# Sheet1.net
KiCad netlist of a schematic drawn in Altium Designer
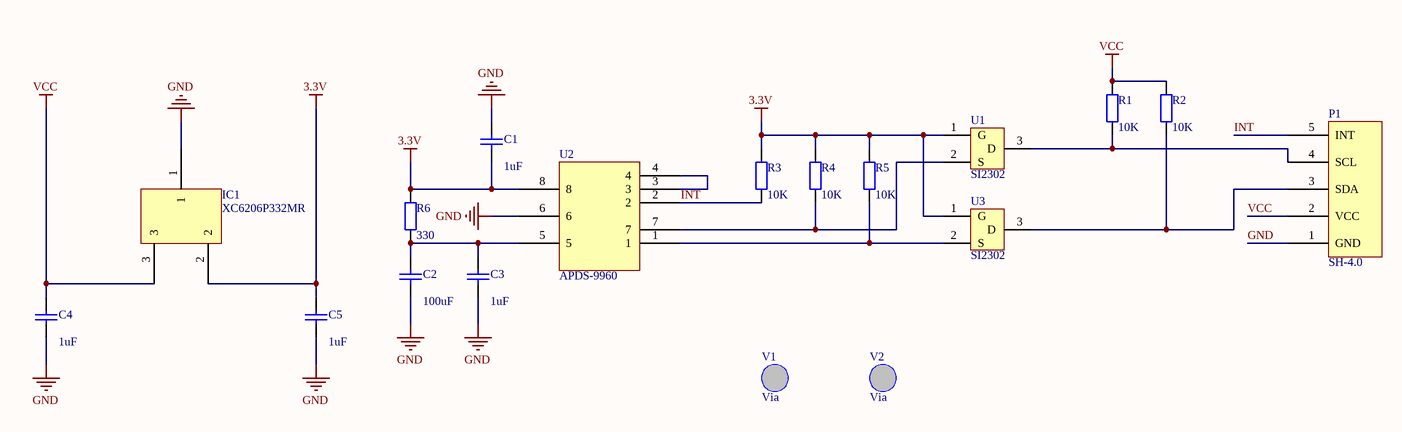
[diagram p0: Sheet1.SchDoc]

(export (version "E")
  (design (tool "Eeschema 10.0.6"))
  (components
    (comp (ref "C1")
      (value "1uF")
      (footprint "1608[0603]")
      (description "Capacitor (Semiconductor SIM Model)")
      (fields (field (name "Comment") "Cap Semi") (field (name "PUBLISHER") "Altium Limited"))
      (libsource (lib "Miscellaneous Devices") (part "Cap Semi"))
    )
    (comp (ref "C2")
      (value "100uF")
      (footprint "C2512")
      (description "Capacitor (Semiconductor SIM Model)")
      (fields (field (name "Comment") "Cap Semi") (field (name "PUBLISHER") "Altium Limited"))
      (libsource (lib "Miscellaneous Devices") (part "Cap Semi"))
    )
    (comp (ref "C3")
      (value "1uF")
      (footprint "1608[0603]")
      (description "Capacitor (Semiconductor SIM Model)")
      (fields (field (name "Comment") "Cap Semi") (field (name "PUBLISHER") "Altium Limited"))
      (libsource (lib "Miscellaneous Devices") (part "Cap Semi"))
    )
    (comp (ref "C4")
      (value "1uF")
      (footprint "1608[0603]")
      (description "Capacitor (Semiconductor SIM Model)")
      (fields (field (name "Comment") "Cap Semi") (field (name "PUBLISHER") "Altium Limited"))
      (libsource (lib "Miscellaneous Devices") (part "Cap Semi"))
    )
    (comp (ref "C5")
      (value "1uF")
      (footprint "1608[0603]")
      (description "Capacitor (Semiconductor SIM Model)")
      (fields (field (name "Comment") "Cap Semi") (field (name "PUBLISHER") "Altium Limited"))
      (libsource (lib "Miscellaneous Devices") (part "Cap Semi"))
    )
    (comp (ref "IC1")
      (value "XC6206P332MR")
      (footprint "PEI_PCB_1.1:SOT-23")
      (libsource (lib "zhaoyujiu") (part "XC6206P332MR"))
    )
    (comp (ref "P1") (value "SH-4.0") (footprint "SH-4.0") (libsource (lib "zhaoyujiu") (part "SH-4.0")))
    (comp (ref "R1")
      (value "10K")
      (footprint "1608[0603]")
      (description "Resistor")
      (fields (field (name "Comment") "Res2") (field (name "PUBLISHER") "Altium Limited"))
      (libsource (lib "Miscellaneous Devices") (part "Res2"))
    )
    (comp (ref "R2")
      (value "10K")
      (footprint "1608[0603]")
      (description "Resistor")
      (fields (field (name "Comment") "Res2") (field (name "PUBLISHER") "Altium Limited"))
      (libsource (lib "Miscellaneous Devices") (part "Res2"))
    )
    (comp (ref "R3")
      (value "10K")
      (footprint "1608[0603]")
      (description "Resistor")
      (fields (field (name "Comment") "Res2") (field (name "PUBLISHER") "Altium Limited"))
      (libsource (lib "Miscellaneous Devices") (part "Res2"))
    )
    (comp (ref "R4")
      (value "10K")
      (footprint "1608[0603]")
      (description "Resistor")
      (fields (field (name "Comment") "Res2") (field (name "PUBLISHER") "Altium Limited"))
      (libsource (lib "Miscellaneous Devices") (part "Res2"))
    )
    (comp (ref "R5")
      (value "10K")
      (footprint "1608[0603]")
      (description "Resistor")
      (fields (field (name "Comment") "Res2") (field (name "PUBLISHER") "Altium Limited"))
      (libsource (lib "Miscellaneous Devices") (part "Res2"))
    )
    (comp (ref "R6")
      (value "330")
      (footprint "1608[0603]")
      (description "Resistor")
      (fields (field (name "Comment") "Res2") (field (name "PUBLISHER") "Altium Limited"))
      (libsource (lib "Miscellaneous Devices") (part "Res2"))
    )
    (comp (ref "U1")
      (value "SI2302")
      (footprint "SOT-23")
      (libsource (lib "PEI_SCH") (part "IRLML2244TRPbF"))
    )
    (comp (ref "U2")
      (value "APDS-9960")
      (footprint "zhaoyujiu:APDS-9960")
      (libsource (lib "zhaoyujiu") (part "APDS-9960"))
    )
    (comp (ref "U3")
      (value "SI2302")
      (footprint "SOT-23")
      (libsource (lib "PEI_SCH") (part "IRLML2244TRPbF"))
    )
    (comp (ref "V1") (value "Via") (footprint "Via") (libsource (lib "zhaoyujiu") (part "Via")))
    (comp (ref "V2") (value "Via") (footprint "Via") (libsource (lib "zhaoyujiu") (part "Via")))
  )
  (nets
    (net (code "1") (name "/INT") (class "Default")
      (node (ref "P1") (pin "5") (pinfunction "INT_5") (pintype "passive"))
      (node (ref "R3") (pin "1") (pinfunction "1_1") (pintype "passive"))
      (node (ref "U2") (pin "2") (pinfunction "2_2") (pintype "passive"))
    )
    (net (code "2") (name "3.3V") (class "Default")
      (node (ref "C1") (pin "2") (pinfunction "2_2") (pintype "passive"))
      (node (ref "C5") (pin "1") (pinfunction "1_1") (pintype "passive"))
      (node (ref "IC1") (pin "2") (pinfunction "2_2") (pintype "passive"))
      (node (ref "R3") (pin "2") (pinfunction "2_2") (pintype "passive"))
      (node (ref "R4") (pin "2") (pinfunction "2_2") (pintype "passive"))
      (node (ref "R5") (pin "2") (pinfunction "2_2") (pintype "passive"))
      (node (ref "R6") (pin "2") (pinfunction "2_2") (pintype "passive"))
      (node (ref "U1") (pin "1") (pinfunction "G_1") (pintype "passive"))
      (node (ref "U2") (pin "8") (pinfunction "8_8") (pintype "passive"))
      (node (ref "U3") (pin "1") (pinfunction "G_1") (pintype "passive"))
    )
    (net (code "3") (name "GND") (class "Default")
      (node (ref "C1") (pin "1") (pinfunction "1_1") (pintype "passive"))
      (node (ref "C2") (pin "2") (pinfunction "2_2") (pintype "passive"))
      (node (ref "C3") (pin "2") (pinfunction "2_2") (pintype "passive"))
      (node (ref "C4") (pin "2") (pinfunction "2_2") (pintype "passive"))
      (node (ref "C5") (pin "2") (pinfunction "2_2") (pintype "passive"))
      (node (ref "IC1") (pin "1") (pinfunction "1_1") (pintype "passive"))
      (node (ref "P1") (pin "1") (pinfunction "GND_1") (pintype "passive"))
      (node (ref "U2") (pin "6") (pinfunction "6_6") (pintype "passive"))
    )
    (net (code "4") (name "Net-(C2-Pad1)") (class "Default")
      (node (ref "C2") (pin "1") (pinfunction "1_1") (pintype "passive"))
      (node (ref "C3") (pin "1") (pinfunction "1_1") (pintype "passive"))
      (node (ref "R6") (pin "1") (pinfunction "1_1") (pintype "passive"))
      (node (ref "U2") (pin "5") (pinfunction "5_5") (pintype "passive"))
    )
    (net (code "5") (name "Net-(P1-SCL)") (class "Default")
      (node (ref "P1") (pin "4") (pinfunction "SCL_4") (pintype "passive"))
      (node (ref "R1") (pin "1") (pinfunction "1_1") (pintype "passive"))
      (node (ref "U1") (pin "3") (pinfunction "D_3") (pintype "passive"))
    )
    (net (code "6") (name "Net-(P1-SDA)") (class "Default")
      (node (ref "P1") (pin "3") (pinfunction "SDA_3") (pintype "passive"))
      (node (ref "R2") (pin "1") (pinfunction "1_1") (pintype "passive"))
      (node (ref "U3") (pin "3") (pinfunction "D_3") (pintype "passive"))
    )
    (net (code "7") (name "Net-(U1-S)") (class "Default")
      (node (ref "R4") (pin "1") (pinfunction "1_1") (pintype "passive"))
      (node (ref "U1") (pin "2") (pinfunction "S_2") (pintype "passive"))
      (node (ref "U2") (pin "7") (pinfunction "7_7") (pintype "passive"))
    )
    (net (code "8") (name "Net-(U2-Pad3)") (class "Default")
      (node (ref "U2") (pin "3") (pinfunction "3_3") (pintype "passive"))
      (node (ref "U2") (pin "4") (pinfunction "4_4") (pintype "passive"))
    )
    (net (code "9") (name "Net-(U3-S)") (class "Default")
      (node (ref "R5") (pin "1") (pinfunction "1_1") (pintype "passive"))
      (node (ref "U2") (pin "1") (pinfunction "1_1") (pintype "passive"))
      (node (ref "U3") (pin "2") (pinfunction "S_2") (pintype "passive"))
    )
    (net (code "10") (name "VCC") (class "Default")
      (node (ref "C4") (pin "1") (pinfunction "1_1") (pintype "passive"))
      (node (ref "IC1") (pin "3") (pinfunction "3_3") (pintype "passive"))
      (node (ref "P1") (pin "2") (pinfunction "VCC_2") (pintype "passive"))
      (node (ref "R1") (pin "2") (pinfunction "2_2") (pintype "passive"))
      (node (ref "R2") (pin "2") (pinfunction "2_2") (pintype "passive"))
    )
  )
)
